# probe_circuit.net
KiCad netlist of a schematic drawn in EAGLE
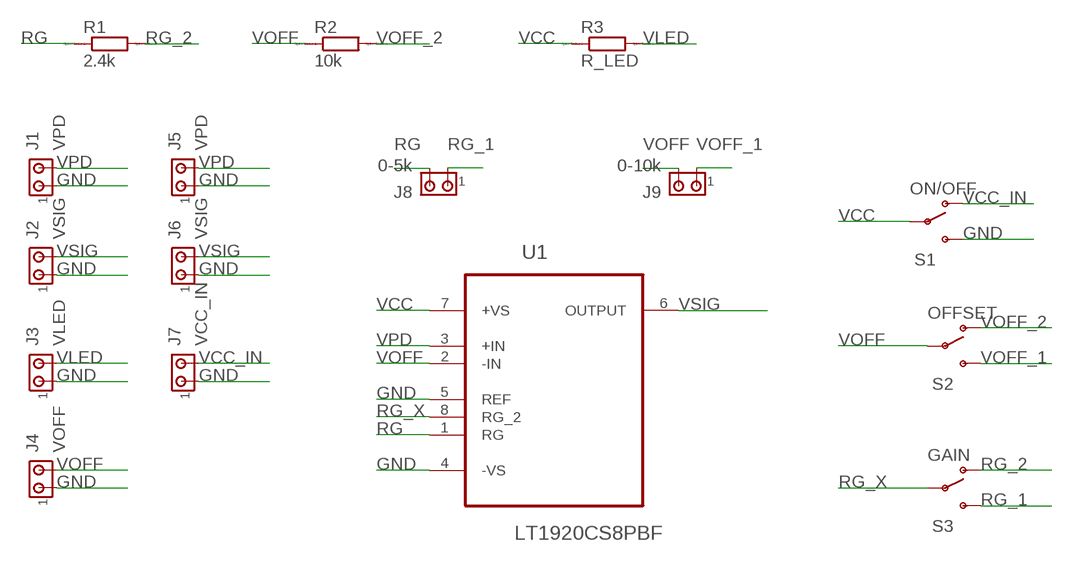
[diagram p0: schematic, sheet 1]

(export (version "E")
  (design (tool "Eeschema 10.0.6"))
  (components
    (comp (ref "J1")
      (value "VPD")
      (footprint "eagle-import:10X02MTA")
      (libsource (lib "eagle-import") (part "MTA02-100"))
    )
    (comp (ref "J2")
      (value "VSIG")
      (footprint "eagle-import:10X02MTA")
      (libsource (lib "eagle-import") (part "MTA02-100"))
    )
    (comp (ref "J3")
      (value "VLED")
      (footprint "eagle-import:10X02MTA")
      (libsource (lib "eagle-import") (part "MTA02-100"))
    )
    (comp (ref "J4")
      (value "VOFF")
      (footprint "eagle-import:10X02MTA")
      (libsource (lib "eagle-import") (part "MTA02-100"))
    )
    (comp (ref "J5")
      (value "VPD")
      (footprint "eagle-import:10X02MTA")
      (libsource (lib "eagle-import") (part "MTA02-100"))
    )
    (comp (ref "J6")
      (value "VSIG")
      (footprint "eagle-import:10X02MTA")
      (libsource (lib "eagle-import") (part "MTA02-100"))
    )
    (comp (ref "J7")
      (value "VCC_IN")
      (footprint "eagle-import:10X02MTA")
      (libsource (lib "eagle-import") (part "MTA02-100"))
    )
    (comp (ref "J8")
      (value "0-5k")
      (footprint "eagle-import:10X02MTA")
      (libsource (lib "eagle-import") (part "MTA02-100"))
    )
    (comp (ref "J9")
      (value "0-10k")
      (footprint "eagle-import:10X02MTA")
      (libsource (lib "eagle-import") (part "MTA02-100"))
    )
    (comp (ref "R1")
      (value "2.4k")
      (footprint "eagle-import:0204_7")
      (libsource (lib "eagle-import") (part "R0204/7"))
    )
    (comp (ref "R2")
      (value "10k")
      (footprint "eagle-import:0204_7")
      (libsource (lib "eagle-import") (part "R0204/7"))
    )
    (comp (ref "R3")
      (value "R_LED")
      (footprint "eagle-import:0204_7")
      (libsource (lib "eagle-import") (part "R0204/7"))
    )
    (comp (ref "S1")
      (value "ON/OFF")
      (footprint "eagle-import:SWITCH-SPDT")
      (libsource (lib "eagle-import") (part "SWITCH-SPDTPTH"))
    )
    (comp (ref "S2")
      (value "OFFSET")
      (footprint "eagle-import:SWITCH-SPDT")
      (libsource (lib "eagle-import") (part "SWITCH-SPDTPTH"))
    )
    (comp (ref "S3")
      (value "GAIN")
      (footprint "eagle-import:SWITCH-SPDT")
      (libsource (lib "eagle-import") (part "SWITCH-SPDTPTH"))
    )
    (comp (ref "U1")
      (value "LT1920CS8PBF")
      (footprint "eagle-import:SOIC127P600X175-8N")
      (fields (field (name "MPN") "LT1920CS8#PBF"))
      (libsource (lib "eagle-import") (part "LT1920CS8PBF"))
    )
  )
  (nets
    (net (code "1") (name "/GND") (class "Default")
      (node (ref "J1") (pin "1") (pinfunction "1_1") (pintype "passive"))
      (node (ref "J2") (pin "1") (pinfunction "1_1") (pintype "passive"))
      (node (ref "J3") (pin "1") (pinfunction "1_1") (pintype "passive"))
      (node (ref "J4") (pin "1") (pinfunction "1_1") (pintype "passive"))
      (node (ref "J5") (pin "1") (pinfunction "1_1") (pintype "passive"))
      (node (ref "J6") (pin "1") (pinfunction "1_1") (pintype "passive"))
      (node (ref "J7") (pin "1") (pinfunction "1_1") (pintype "passive"))
      (node (ref "S1") (pin "3") (pinfunction "S_3") (pintype "passive"))
      (node (ref "U1") (pin "4") (pinfunction "-VS_4") (pintype "power_in"))
      (node (ref "U1") (pin "5") (pinfunction "REF_5") (pintype "input"))
    )
    (net (code "2") (name "/RG") (class "Default")
      (node (ref "J8") (pin "2") (pinfunction "2_2") (pintype "passive"))
      (node (ref "R1") (pin "1") (pinfunction "1_1") (pintype "passive"))
      (node (ref "U1") (pin "1") (pinfunction "RG_1") (pintype "passive"))
    )
    (net (code "3") (name "/RG_1") (class "Default")
      (node (ref "J8") (pin "1") (pinfunction "1_1") (pintype "passive"))
      (node (ref "S3") (pin "3") (pinfunction "S_3") (pintype "passive"))
    )
    (net (code "4") (name "/RG_2") (class "Default")
      (node (ref "R1") (pin "2") (pinfunction "2_2") (pintype "passive"))
      (node (ref "S3") (pin "1") (pinfunction "O_1") (pintype "passive"))
    )
    (net (code "5") (name "/RG_X") (class "Default")
      (node (ref "S3") (pin "2") (pinfunction "P_2") (pintype "passive"))
      (node (ref "U1") (pin "8") (pinfunction "RG_2_8") (pintype "passive"))
    )
    (net (code "6") (name "/VCC") (class "Default")
      (node (ref "R3") (pin "1") (pinfunction "1_1") (pintype "passive"))
      (node (ref "S1") (pin "2") (pinfunction "P_2") (pintype "passive"))
      (node (ref "U1") (pin "7") (pinfunction "+VS_7") (pintype "power_in"))
    )
    (net (code "7") (name "/VCC_IN") (class "Default")
      (node (ref "J7") (pin "2") (pinfunction "2_2") (pintype "passive"))
      (node (ref "S1") (pin "1") (pinfunction "O_1") (pintype "passive"))
    )
    (net (code "8") (name "/VLED") (class "Default")
      (node (ref "J3") (pin "2") (pinfunction "2_2") (pintype "passive"))
      (node (ref "R3") (pin "2") (pinfunction "2_2") (pintype "passive"))
    )
    (net (code "9") (name "/VOFF") (class "Default")
      (node (ref "J4") (pin "2") (pinfunction "2_2") (pintype "passive"))
      (node (ref "J9") (pin "2") (pinfunction "2_2") (pintype "passive"))
      (node (ref "R2") (pin "1") (pinfunction "1_1") (pintype "passive"))
      (node (ref "S2") (pin "2") (pinfunction "P_2") (pintype "passive"))
      (node (ref "U1") (pin "2") (pinfunction "-IN_2") (pintype "input"))
    )
    (net (code "10") (name "/VOFF_1") (class "Default")
      (node (ref "J9") (pin "1") (pinfunction "1_1") (pintype "passive"))
      (node (ref "S2") (pin "3") (pinfunction "S_3") (pintype "passive"))
    )
    (net (code "11") (name "/VOFF_2") (class "Default")
      (node (ref "R2") (pin "2") (pinfunction "2_2") (pintype "passive"))
      (node (ref "S2") (pin "1") (pinfunction "O_1") (pintype "passive"))
    )
    (net (code "12") (name "/VPD") (class "Default")
      (node (ref "J1") (pin "2") (pinfunction "2_2") (pintype "passive"))
      (node (ref "J5") (pin "2") (pinfunction "2_2") (pintype "passive"))
      (node (ref "U1") (pin "3") (pinfunction "+IN_3") (pintype "input"))
    )
    (net (code "13") (name "/VSIG") (class "Default")
      (node (ref "J2") (pin "2") (pinfunction "2_2") (pintype "passive"))
      (node (ref "J6") (pin "2") (pinfunction "2_2") (pintype "passive"))
      (node (ref "U1") (pin "6") (pinfunction "OUTPUT_6") (pintype "output"))
    )
  )
)
